# Logic.net
KiCad netlist of a schematic drawn in Altium Designer
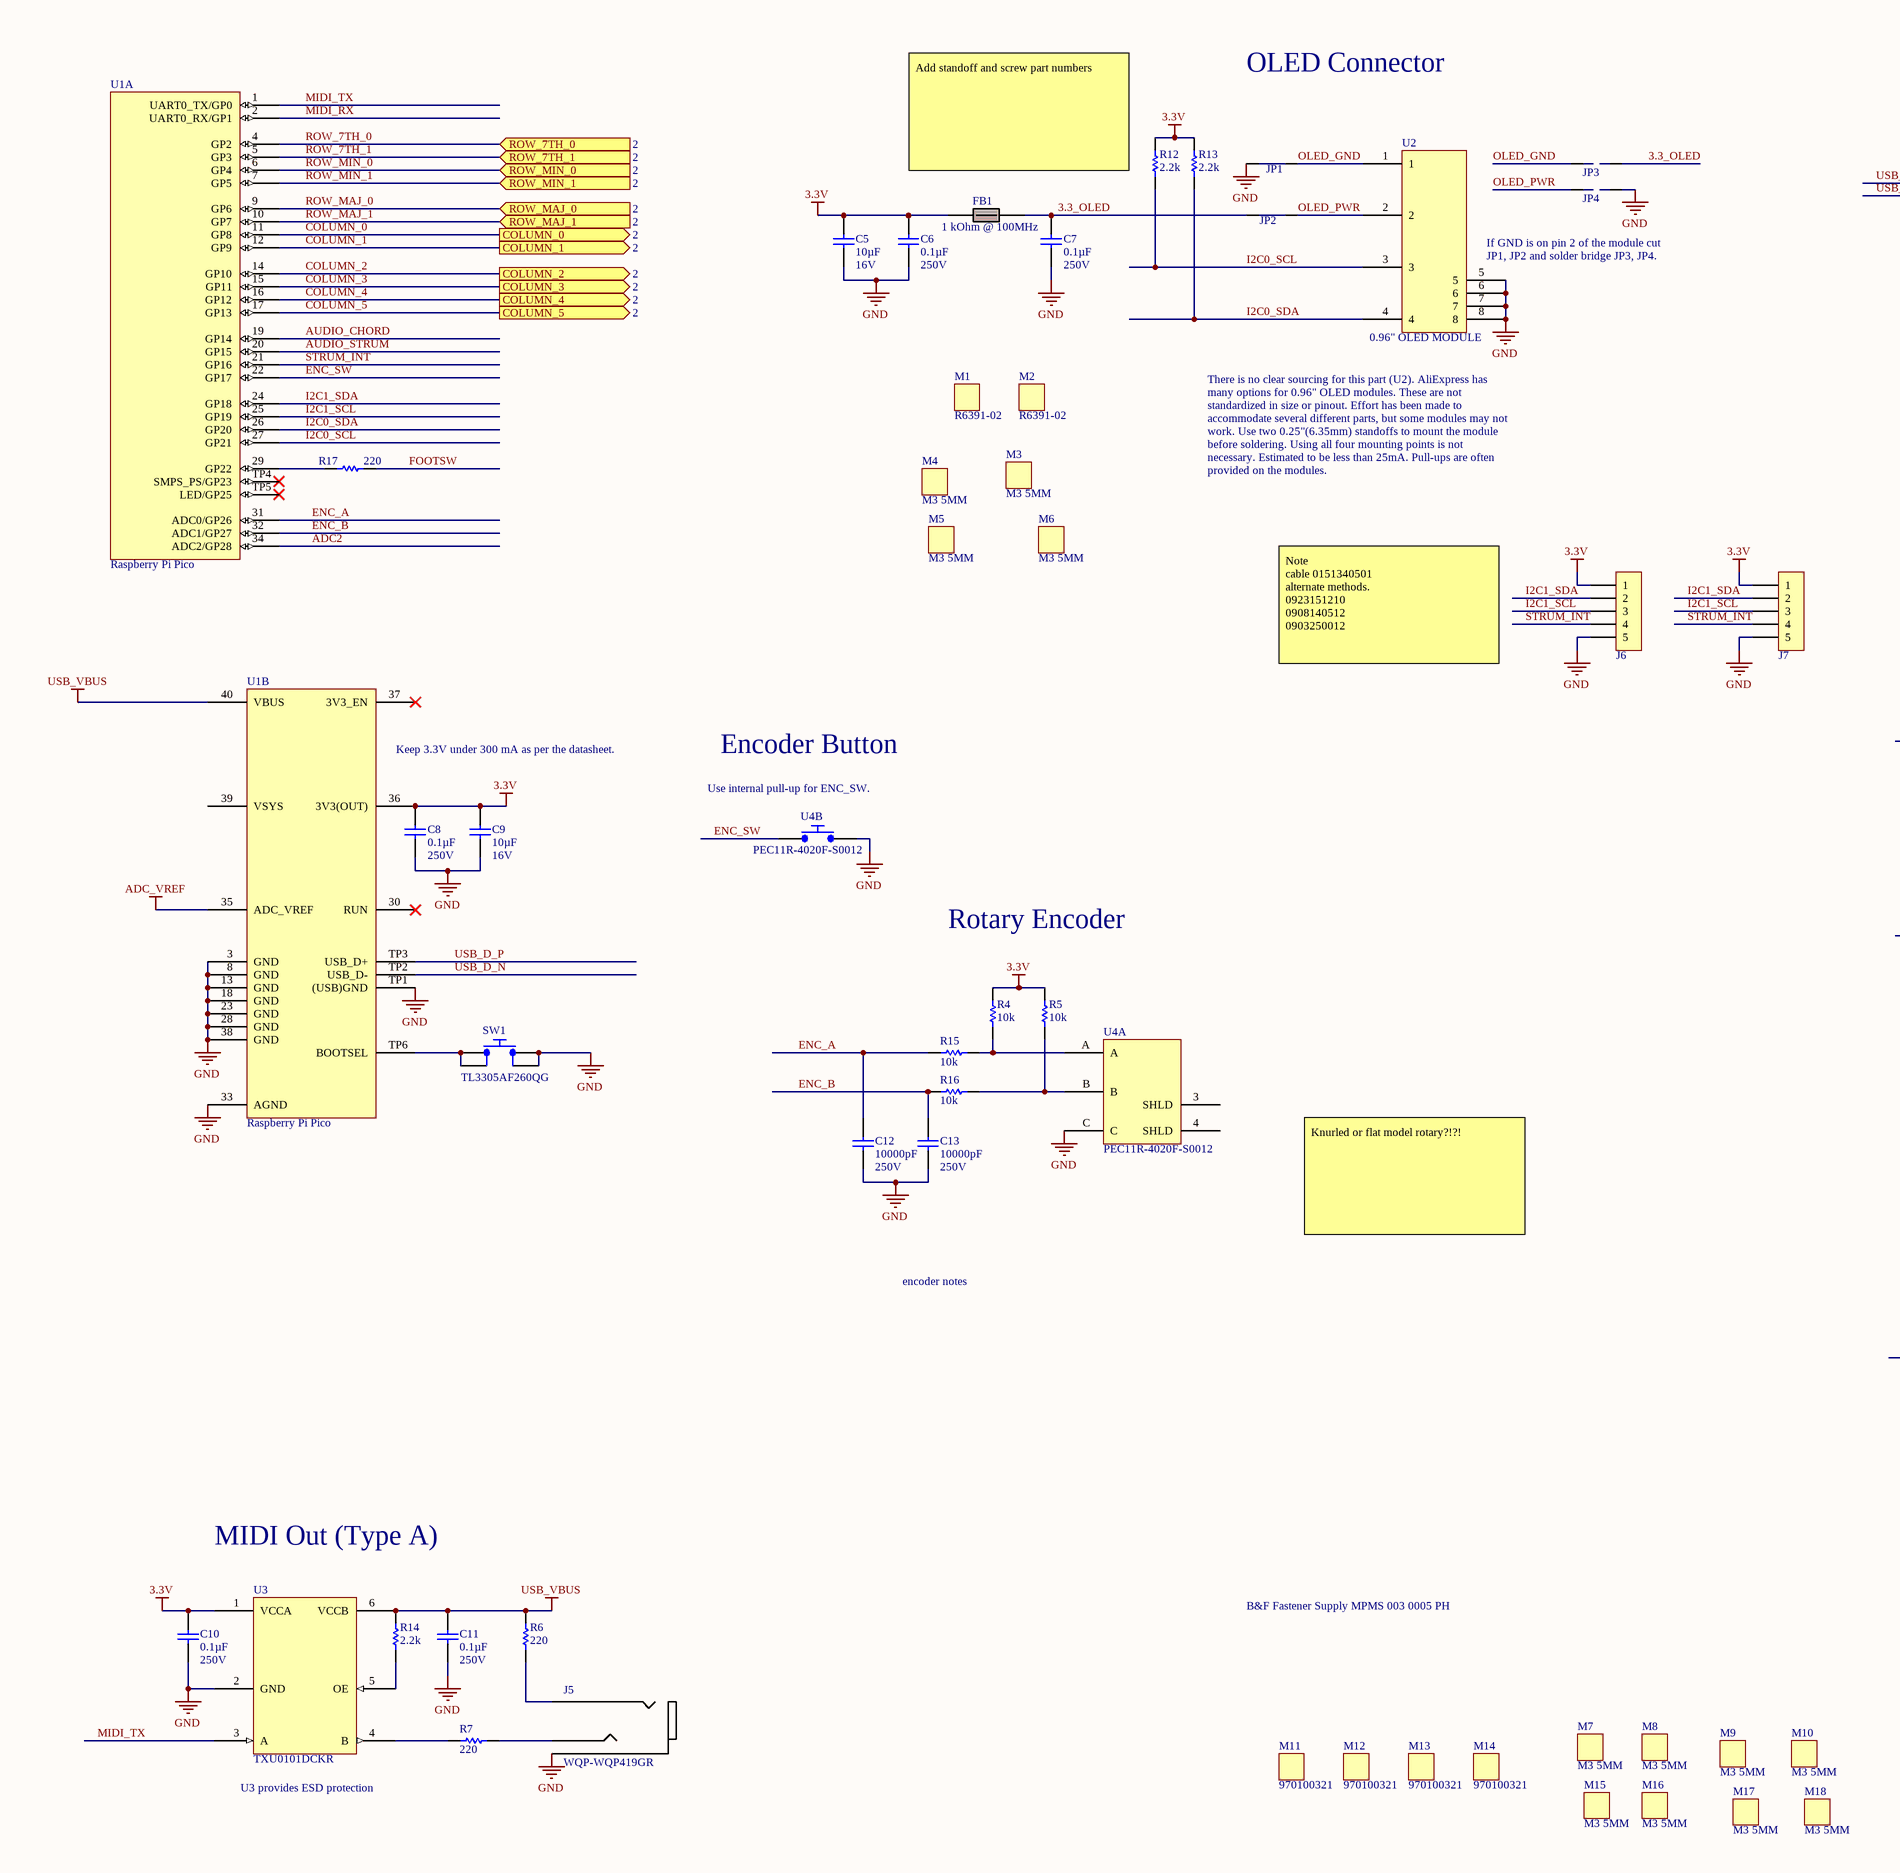
[diagram p0: Logic.SchDoc, left]
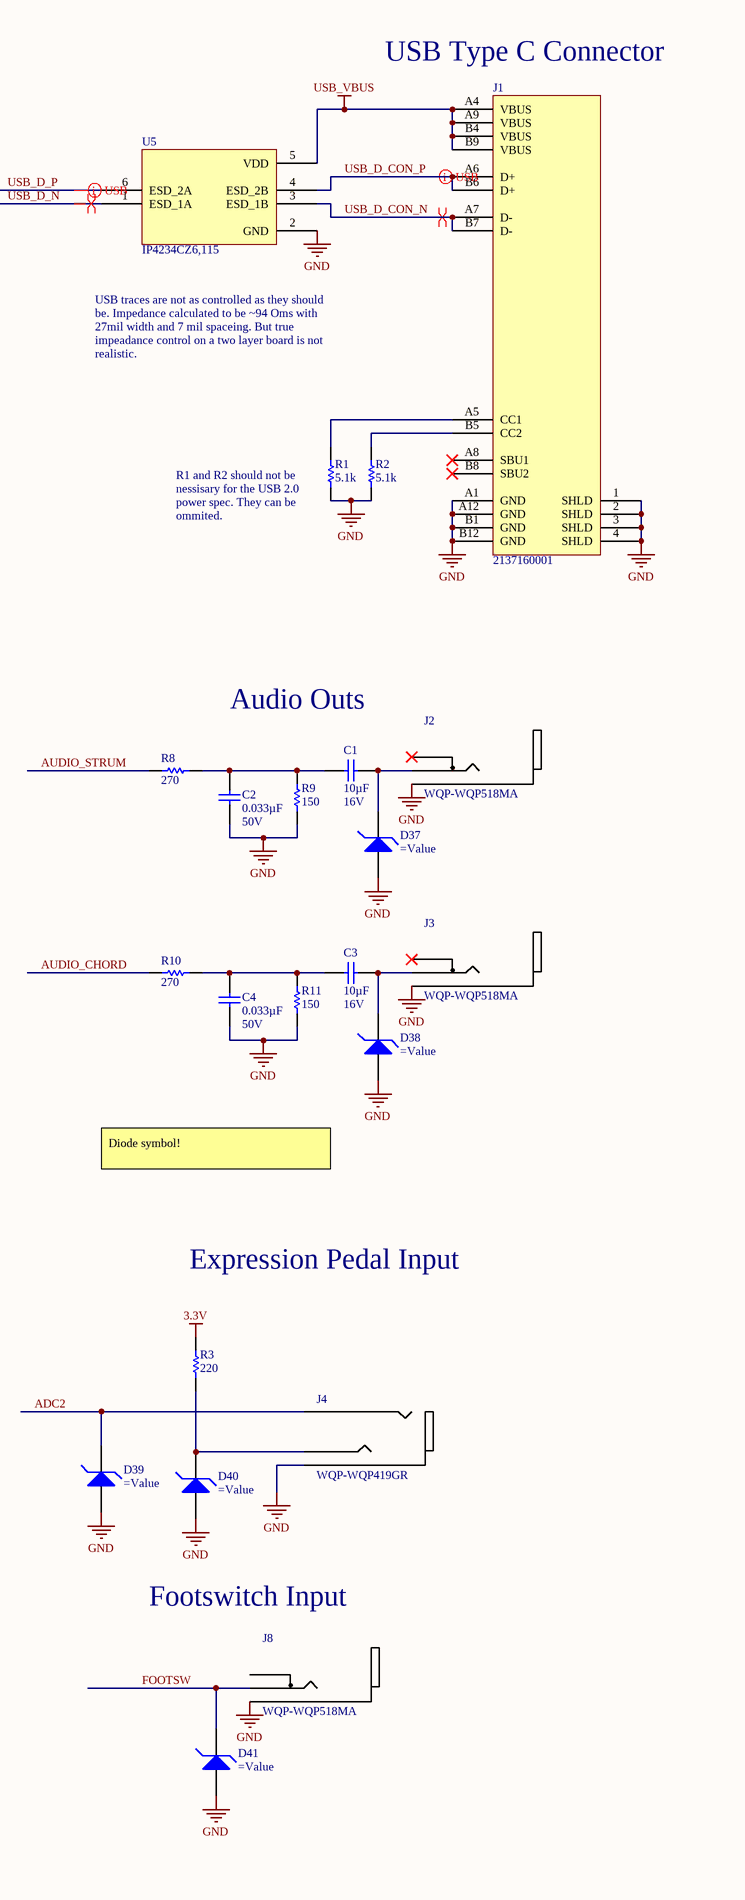
[diagram p1: Logic.SchDoc, right]

(export (version "E")
  (design (tool "Eeschema 10.0.6"))
  (components
    (comp (ref "C1")
      (value "10µF")
      (footprint "Chip0805")
      (description "CAP CER 10UF 16V 10% X5R 0805")
      (fields
        (field (name "VOLTAGE") "16V")
        (field (name "PARTNUMBER") "C2012X5R1C106K125AC")
        (field (name "MANUFACTURER") "TDK Corporation")
      )
      (libsource (lib "Passives") (part "CAP"))
    )
    (comp (ref "C2")
      (value "0.033µF")
      (footprint "Chip0805")
      (description "CAP CER 0.033UF 50V 5% NP0 0805")
      (fields
        (field (name "VOLTAGE") "50V")
        (field (name "PARTNUMBER") "C2012C0G1H333J125AA")
        (field (name "MANUFACTURER") "TDK Corporation")
      )
      (libsource (lib "Passives") (part "CAP"))
    )
    (comp (ref "C3")
      (value "10µF")
      (footprint "Chip0805")
      (description "CAP CER 10UF 16V 10% X5R 0805")
      (fields
        (field (name "VOLTAGE") "16V")
        (field (name "PARTNUMBER") "C2012X5R1C106K125AC")
        (field (name "MANUFACTURER") "TDK Corporation")
      )
      (libsource (lib "Passives") (part "CAP"))
    )
    (comp (ref "C4")
      (value "0.033µF")
      (footprint "Chip0805")
      (description "CAP CER 0.033UF 50V 5% NP0 0805")
      (fields
        (field (name "VOLTAGE") "50V")
        (field (name "PARTNUMBER") "C2012C0G1H333J125AA")
        (field (name "MANUFACTURER") "TDK Corporation")
      )
      (libsource (lib "Passives") (part "CAP"))
    )
    (comp (ref "C5")
      (value "10µF")
      (footprint "Chip0805")
      (description "CAP CER 10UF 16V 10% X5R 0805")
      (fields
        (field (name "VOLTAGE") "16V")
        (field (name "PARTNUMBER") "C2012X5R1C106K125AC")
        (field (name "MANUFACTURER") "TDK Corporation")
      )
      (libsource (lib "Passives") (part "CAP"))
    )
    (comp (ref "C6")
      (value "0.1µF")
      (footprint "Chip0805")
      (description "CAP CER 0.1UF 250V 10% X7T 0805")
      (fields
        (field (name "VOLTAGE") "250V")
        (field (name "PARTNUMBER") "C2012X7T2E104K125AA")
        (field (name "MANUFACTURER") "TDK Corporation")
      )
      (libsource (lib "Passives") (part "CAP"))
    )
    (comp (ref "C7")
      (value "0.1µF")
      (footprint "Chip0805")
      (description "CAP CER 0.1UF 250V 10% X7T 0805")
      (fields
        (field (name "VOLTAGE") "250V")
        (field (name "PARTNUMBER") "C2012X7T2E104K125AA")
        (field (name "MANUFACTURER") "TDK Corporation")
      )
      (libsource (lib "Passives") (part "CAP"))
    )
    (comp (ref "C8")
      (value "0.1µF")
      (footprint "Chip0805")
      (description "CAP CER 0.1UF 250V 10% X7T 0805")
      (fields
        (field (name "VOLTAGE") "250V")
        (field (name "PARTNUMBER") "C2012X7T2E104K125AA")
        (field (name "MANUFACTURER") "TDK Corporation")
      )
      (libsource (lib "Passives") (part "CAP"))
    )
    (comp (ref "C9")
      (value "10µF")
      (footprint "Chip0805")
      (description "CAP CER 10UF 16V 10% X5R 0805")
      (fields
        (field (name "VOLTAGE") "16V")
        (field (name "PARTNUMBER") "C2012X5R1C106K125AC")
        (field (name "MANUFACTURER") "TDK Corporation")
      )
      (libsource (lib "Passives") (part "CAP"))
    )
    (comp (ref "C10")
      (value "0.1µF")
      (footprint "Chip0805")
      (description "CAP CER 0.1UF 250V 10% X7T 0805")
      (fields
        (field (name "VOLTAGE") "250V")
        (field (name "PARTNUMBER") "C2012X7T2E104K125AA")
        (field (name "MANUFACTURER") "TDK Corporation")
      )
      (libsource (lib "Passives") (part "CAP"))
    )
    (comp (ref "C11")
      (value "0.1µF")
      (footprint "Chip0805")
      (description "CAP CER 0.1UF 250V 10% X7T 0805")
      (fields
        (field (name "VOLTAGE") "250V")
        (field (name "PARTNUMBER") "C2012X7T2E104K125AA")
        (field (name "MANUFACTURER") "TDK Corporation")
      )
      (libsource (lib "Passives") (part "CAP"))
    )
    (comp (ref "C12")
      (value "10000pF")
      (footprint "Chip0805")
      (description "CAP CER 10000PF 250V X7R 0805")
      (fields
        (field (name "VOLTAGE") "250V")
        (field (name "PARTNUMBER") "C2012X7R2E103M125AE")
        (field (name "MANUFACTURER") "TDK Corporation")
      )
      (libsource (lib "Passives") (part "CAP"))
    )
    (comp (ref "C13")
      (value "10000pF")
      (footprint "Chip0805")
      (description "CAP CER 10000PF 250V X7R 0805")
      (fields
        (field (name "VOLTAGE") "250V")
        (field (name "PARTNUMBER") "C2012X7R2E103M125AE")
        (field (name "MANUFACTURER") "TDK Corporation")
      )
      (libsource (lib "Passives") (part "CAP"))
    )
    (comp (ref "D37")
      (value "~")
      (footprint "SOD-923")
      (description "TVS DIODE 3.3VWM 10.4VC SOD923")
      (fields (field (name "PARTNUMBER") "SZESD9X3.3ST5G") (field (name "MANUFACTURER") "onsemi"))
      (libsource (lib "Semiconductor") (part "DIODE_ZENER"))
    )
    (comp (ref "D38")
      (value "~")
      (footprint "SOD-923")
      (description "TVS DIODE 3.3VWM 10.4VC SOD923")
      (fields (field (name "PARTNUMBER") "SZESD9X3.3ST5G") (field (name "MANUFACTURER") "onsemi"))
      (libsource (lib "Semiconductor") (part "DIODE_ZENER"))
    )
    (comp (ref "D39")
      (value "~")
      (footprint "SOD-923")
      (description "TVS DIODE 3.3VWM 10.4VC SOD923")
      (fields (field (name "PARTNUMBER") "SZESD9X3.3ST5G") (field (name "MANUFACTURER") "onsemi"))
      (libsource (lib "Semiconductor") (part "DIODE_ZENER"))
    )
    (comp (ref "D40")
      (value "~")
      (footprint "SOD-923")
      (description "TVS DIODE 3.3VWM 10.4VC SOD923")
      (fields (field (name "PARTNUMBER") "SZESD9X3.3ST5G") (field (name "MANUFACTURER") "onsemi"))
      (libsource (lib "Semiconductor") (part "DIODE_ZENER"))
    )
    (comp (ref "D41")
      (value "~")
      (footprint "SOD-923")
      (description "TVS DIODE 3.3VWM 10.4VC SOD923")
      (fields (field (name "PARTNUMBER") "SZESD9X3.3ST5G") (field (name "MANUFACTURER") "onsemi"))
      (libsource (lib "Semiconductor") (part "DIODE_ZENER"))
    )
    (comp (ref "FB1")
      (value "FERRITE")
      (footprint "Chip0805")
      (description "FERRITE BEAD 1000 OHM .20A 0805")
      (fields
        (field (name "IMPEDANCE @ FREQUENCY") "1 kOhm @ 100MHz")
        (field (name "PARTNUMBER") "74279205")
        (field (name "MANUFACTURER") "Wurth Electronics Inc")
      )
      (libsource (lib "Passives") (part "FERRITE"))
    )
    (comp (ref "J1")
      (value "2137160001")
      (footprint "MOLEX_2137160001")
      (description "CONN RCPT USB2.0 TYPE C 24POS RA")
      (fields (field (name "MANUFACTURER") "Molex, LLC"))
      (libsource (lib "Connectors") (part "MOLEX_2137160001"))
    )
    (comp (ref "J2")
      (value "WQP-WQP518MA")
      (footprint "PJ301M-12")
      (description "CONN 3.5mm VIRTICAL MONO w/ NORMAL")
      (fields (field (name "MANUFACTURER") "QingPu"))
      (libsource (lib "Connectors") (part "PJ301M-12"))
    )
    (comp (ref "J3")
      (value "WQP-WQP518MA")
      (footprint "PJ301M-12")
      (description "CONN 3.5mm VIRTICAL MONO w/ NORMAL")
      (fields (field (name "MANUFACTURER") "QingPu"))
      (libsource (lib "Connectors") (part "PJ301M-12"))
    )
    (comp (ref "J4")
      (value "WQP-WQP419GR")
      (footprint "PJ366ST")
      (description "CONN 3.5mm VIRTICAL STEREO")
      (fields (field (name "MANUFACTURER") "QingPu"))
      (libsource (lib "Connectors") (part "PJ366ST"))
    )
    (comp (ref "J5")
      (value "WQP-WQP419GR")
      (footprint "PJ366ST")
      (description "CONN 3.5mm VIRTICAL STEREO")
      (fields (field (name "MANUFACTURER") "QingPu"))
      (libsource (lib "Connectors") (part "PJ366ST"))
    )
    (comp (ref "J6")
      (value "0532610571")
      (footprint "MOLEX_0532610571")
      (description "CONN HEADER SMD R/A 5POS 1.25MM")
      (fields (field (name "MANUFACTURER PART NUMBER") "WM7623CT-ND") (field (name "MANUFACTURER") "Molex"))
      (libsource (lib "Connectors") (part "HEADER_1x5"))
    )
    (comp (ref "J7")
      (value "250010502")
      (footprint "HEADER_1x5_100mil_NP")
      (description "CABLE 5POS .100 JUMPER 2 INCHES")
      (fields (field (name "MANUFACTURER") "Molex Inc"))
      (libsource (lib "Cable_Assemblies") (part "HEADER_1x5"))
    )
    (comp (ref "J8")
      (value "WQP-WQP518MA")
      (footprint "PJ301M-12")
      (description "CONN 3.5mm VIRTICAL MONO w/ NORMAL")
      (fields (field (name "MANUFACTURER") "QingPu"))
      (libsource (lib "Connectors") (part "PJ301M-12"))
    )
    (comp (ref "JP1")
      (value "JUMMPER_NC_0805")
      (footprint "JUMMPER_NC_0805")
      (libsource (lib "Mechanical") (part "JUMPER_NC"))
    )
    (comp (ref "JP2")
      (value "JUMMPER_NC_0805")
      (footprint "JUMMPER_NC_0805")
      (libsource (lib "Mechanical") (part "JUMPER_NC"))
    )
    (comp (ref "JP3")
      (value "JUMMPER_NO_0805")
      (footprint "JUMMPER_NO_0805")
      (libsource (lib "Mechanical") (part "JUMPER_NO"))
    )
    (comp (ref "JP4")
      (value "JUMMPER_NO_0805")
      (footprint "JUMMPER_NO_0805")
      (libsource (lib "Mechanical") (part "JUMPER_NO"))
    )
    (comp (ref "M1")
      (value "R6391-02")
      (description "HEX STANDOFF M3X0.5 BRASS 1/4\"")
      (fields (field (name "MANUFACTURER") "Harwin Inc."))
      (libsource (lib "Mechanical") (part "MECH_NO_FP"))
    )
    (comp (ref "M2")
      (value "R6391-02")
      (description "HEX STANDOFF M3X0.5 BRASS 1/4\"")
      (fields (field (name "MANUFACTURER") "Harwin Inc."))
      (libsource (lib "Mechanical") (part "MECH_NO_FP"))
    )
    (comp (ref "M3")
      (value "M3 5MM")
      (description "MACH SCREW PAN HEAD PHILLIPS M3 5MM")
      (libsource (lib "Mechanical") (part "MECH_NO_FP"))
    )
    (comp (ref "M4")
      (value "M3 5MM")
      (description "MACH SCREW PAN HEAD PHILLIPS M3 5MM")
      (libsource (lib "Mechanical") (part "MECH_NO_FP"))
    )
    (comp (ref "M5")
      (value "M3 5MM")
      (description "MACH SCREW PAN HEAD PHILLIPS M3 5MM")
      (libsource (lib "Mechanical") (part "MECH_NO_FP"))
    )
    (comp (ref "M6")
      (value "M3 5MM")
      (description "MACH SCREW PAN HEAD PHILLIPS M3 5MM")
      (libsource (lib "Mechanical") (part "MECH_NO_FP"))
    )
    (comp (ref "M7")
      (value "M3 5MM")
      (description "MACH SCREW PAN HEAD PHILLIPS M3 5MM")
      (libsource (lib "Mechanical") (part "MECH_NO_FP"))
    )
    (comp (ref "M8")
      (value "M3 5MM")
      (description "MACH SCREW PAN HEAD PHILLIPS M3 5MM")
      (libsource (lib "Mechanical") (part "MECH_NO_FP"))
    )
    (comp (ref "M9")
      (value "M3 5MM")
      (description "MACH SCREW PAN HEAD PHILLIPS M3 5MM")
      (libsource (lib "Mechanical") (part "MECH_NO_FP"))
    )
    (comp (ref "M10")
      (value "M3 5MM")
      (description "MACH SCREW PAN HEAD PHILLIPS M3 5MM")
      (libsource (lib "Mechanical") (part "MECH_NO_FP"))
    )
    (comp (ref "M11")
      (value "970100321")
      (description "HEX STANDOFF M3X0.5 STEEL 10MM")
      (fields (field (name "MANUFACTURER") "Würth Elektronik"))
      (libsource (lib "Mechanical") (part "MECH_NO_FP"))
    )
    (comp (ref "M12")
      (value "970100321")
      (description "HEX STANDOFF M3X0.5 STEEL 10MM")
      (fields (field (name "MANUFACTURER") "Würth Elektronik"))
      (libsource (lib "Mechanical") (part "MECH_NO_FP"))
    )
    (comp (ref "M13")
      (value "970100321")
      (description "HEX STANDOFF M3X0.5 STEEL 10MM")
      (fields (field (name "MANUFACTURER") "Würth Elektronik"))
      (libsource (lib "Mechanical") (part "MECH_NO_FP"))
    )
    (comp (ref "M14")
      (value "970100321")
      (description "HEX STANDOFF M3X0.5 STEEL 10MM")
      (fields (field (name "MANUFACTURER") "Würth Elektronik"))
      (libsource (lib "Mechanical") (part "MECH_NO_FP"))
    )
    (comp (ref "M15")
      (value "M3 5MM")
      (description "MACH SCREW PAN HEAD PHILLIPS M3 5MM")
      (libsource (lib "Mechanical") (part "MECH_NO_FP"))
    )
    (comp (ref "M16")
      (value "M3 5MM")
      (description "MACH SCREW PAN HEAD PHILLIPS M3 5MM")
      (libsource (lib "Mechanical") (part "MECH_NO_FP"))
    )
    (comp (ref "M17")
      (value "M3 5MM")
      (description "MACH SCREW PAN HEAD PHILLIPS M3 5MM")
      (libsource (lib "Mechanical") (part "MECH_NO_FP"))
    )
    (comp (ref "M18")
      (value "M3 5MM")
      (description "MACH SCREW PAN HEAD PHILLIPS M3 5MM")
      (libsource (lib "Mechanical") (part "MECH_NO_FP"))
    )
    (comp (ref "R1")
      (value "5.1k")
      (footprint "Chip0603")
      (description "RES 5.10K OHM 1/10W 1% 0603 SMD")
      (fields (field (name "PARTNUMBER") "CRCW06035K10FKEA") (field (name "MANUFACTURER") "Vishay Dale"))
      (libsource (lib "Passives") (part "RES"))
    )
    (comp (ref "R2")
      (value "5.1k")
      (footprint "Chip0603")
      (description "RES 5.10K OHM 1/10W 1% 0603 SMD")
      (fields (field (name "PARTNUMBER") "CRCW06035K10FKEA") (field (name "MANUFACTURER") "Vishay Dale"))
      (libsource (lib "Passives") (part "RES"))
    )
    (comp (ref "R3")
      (value "220")
      (footprint "Chip0805")
      (description "RES 220 OHM 1/8W 1% 0805 SMD")
      (fields (field (name "PARTNUMBER") "CRCW0805220RFKEA") (field (name "MANUFACTURER") "Vishay Dale"))
      (libsource (lib "Passives") (part "RES"))
    )
    (comp (ref "R4")
      (value "10k")
      (footprint "Chip0805")
      (description "RES 10.0K OHM 1/8W 1% 0805 SMD")
      (fields (field (name "PARTNUMBER") "CRCW080510K0FKEA") (field (name "MANUFACTURER") "Vishay Dale"))
      (libsource (lib "Passives") (part "RES"))
    )
    (comp (ref "R5")
      (value "10k")
      (footprint "Chip0805")
      (description "RES 10.0K OHM 1/8W 1% 0805 SMD")
      (fields (field (name "PARTNUMBER") "CRCW080510K0FKEA") (field (name "MANUFACTURER") "Vishay Dale"))
      (libsource (lib "Passives") (part "RES"))
    )
    (comp (ref "R6")
      (value "220")
      (footprint "Chip0805")
      (description "RES 220 OHM 1/8W 1% 0805 SMD")
      (fields (field (name "PARTNUMBER") "CRCW0805220RFKEA") (field (name "MANUFACTURER") "Vishay Dale"))
      (libsource (lib "Passives") (part "RES"))
    )
    (comp (ref "R7")
      (value "220")
      (footprint "Chip0805")
      (description "RES 220 OHM 1/8W 1% 0805 SMD")
      (fields (field (name "PARTNUMBER") "CRCW0805220RFKEA") (field (name "MANUFACTURER") "Vishay Dale"))
      (libsource (lib "Passives") (part "RES"))
    )
    (comp (ref "R8")
      (value "270")
      (footprint "Chip0805")
      (description "RES 270 OHM 1/8W 1% 0805 SMD")
      (fields (field (name "PARTNUMBER") "CRCW0805270RFKEA") (field (name "MANUFACTURER") "Vishay Dale"))
      (libsource (lib "Passives") (part "RES"))
    )
    (comp (ref "R9")
      (value "150")
      (footprint "Chip0805")
      (description "RES 150 OHM 1/8W 1% 0805 SMD")
      (fields (field (name "PARTNUMBER") "CRCW0805150RFKEA") (field (name "MANUFACTURER") "Vishay Dale"))
      (libsource (lib "Passives") (part "RES"))
    )
    (comp (ref "R10")
      (value "270")
      (footprint "Chip0805")
      (description "RES 270 OHM 1/8W 1% 0805 SMD")
      (fields (field (name "PARTNUMBER") "CRCW0805270RFKEA") (field (name "MANUFACTURER") "Vishay Dale"))
      (libsource (lib "Passives") (part "RES"))
    )
    (comp (ref "R11")
      (value "150")
      (footprint "Chip0805")
      (description "RES 150 OHM 1/8W 1% 0805 SMD")
      (fields (field (name "PARTNUMBER") "CRCW0805150RFKEA") (field (name "MANUFACTURER") "Vishay Dale"))
      (libsource (lib "Passives") (part "RES"))
    )
    (comp (ref "R12")
      (value "2.2k")
      (footprint "Chip0805")
      (description "RES 2.20K OHM 1/8W 1% 0805 SMD")
      (fields (field (name "PARTNUMBER") "CRCW08052K20FKEA") (field (name "MANUFACTURER") "Vishay Dale"))
      (libsource (lib "Passives") (part "RES"))
    )
    (comp (ref "R13")
      (value "2.2k")
      (footprint "Chip0805")
      (description "RES 2.20K OHM 1/8W 1% 0805 SMD")
      (fields (field (name "PARTNUMBER") "CRCW08052K20FKEA") (field (name "MANUFACTURER") "Vishay Dale"))
      (libsource (lib "Passives") (part "RES"))
    )
    (comp (ref "R14")
      (value "2.2k")
      (footprint "Chip0805")
      (description "RES 2.20K OHM 1/8W 1% 0805 SMD")
      (fields (field (name "PARTNUMBER") "CRCW08052K20FKEA") (field (name "MANUFACTURER") "Vishay Dale"))
      (libsource (lib "Passives") (part "RES"))
    )
    (comp (ref "R15")
      (value "10k")
      (footprint "Chip0805")
      (description "RES 10.0K OHM 1/8W 1% 0805 SMD")
      (fields (field (name "PARTNUMBER") "CRCW080510K0FKEA") (field (name "MANUFACTURER") "Vishay Dale"))
      (libsource (lib "Passives") (part "RES"))
    )
    (comp (ref "R16")
      (value "10k")
      (footprint "Chip0805")
      (description "RES 10.0K OHM 1/8W 1% 0805 SMD")
      (fields (field (name "PARTNUMBER") "CRCW080510K0FKEA") (field (name "MANUFACTURER") "Vishay Dale"))
      (libsource (lib "Passives") (part "RES"))
    )
    (comp (ref "R17")
      (value "220")
      (footprint "Chip0805")
      (description "RES 220 OHM 1/8W 1% 0805 SMD")
      (fields (field (name "PARTNUMBER") "CRCW0805220RFKEA") (field (name "MANUFACTURER") "Vishay Dale"))
      (libsource (lib "Passives") (part "RES"))
    )
    (comp (ref "SW1")
      (value "TL3305AF260QG")
      (footprint "E_SWITCH_TL3305")
      (description "SWITCH TACTILE SPST-NO 50MA 12V")
      (fields (field (name "MANUFACTURER") "E-Switch"))
      (libsource (lib "Switches") (part "SWITCH_SPST_PUSH_NO_4"))
    )
    (comp (ref "U1")
      (value "Raspberry Pi Pico")
      (footprint "RASPBERRY_PI_PICO")
      (description "RASPBERRY PI PICO RP2040 BOARD")
      (fields (field (name "MANUFACTURER PART NUMBER") "SC0915") (field (name "MANUFACTURER") "Raspberry Pi"))
      (libsource (lib "ICs") (part "PI_PICO_SC0915"))
    )
    (comp (ref "U2")
      (value "0.96\" OLED MODULE")
      (footprint "OLEDp96MOD_BOARD_MOUNT")
      (description "0.96\" I2C OLED MODULE")
      (libsource (lib "ICs") (part "OLEDp96MOD_BOARD_MOUNT"))
    )
    (comp (ref "U3")
      (value "TXU0101DCKR")
      (footprint "6-TSSOP")
      (description "SINGLE CHANNEL FIXED-DIRECTION L")
      (fields (field (name "MANUFACTURER") "Texas Instruments"))
      (libsource (lib "ICs") (part "TI_TXU0101"))
    )
    (comp (ref "U4")
      (value "PEC11R-4020F-S0012")
      (footprint "BOURNS_PEC11R-4020F-S")
      (description "ROTARY ENCODER MECHANICAL 12PPR")
      (fields (field (name "MANUFACTURER") "Bourns Inc."))
      (libsource (lib "Miscellaneous") (part "ROTARY_ENCODER_SWITCH"))
    )
    (comp (ref "U5")
      (value "IP4234CZ6,115")
      (footprint "6-TSOP")
      (description "TVS DIODE 5.5VWM 6TSOP")
      (fields (field (name "MANUFACTURER") "Nexperia USA Inc."))
      (libsource (lib "Semiconductor") (part "NEXPERIA_IP4234CZ6"))
    )
  )
  (nets
    (net (code "1") (name "/3.3_OLED") (class "Default")
      (node (ref "C7") (pin "2") (pinfunction "2_2") (pintype "passive"))
      (node (ref "FB1") (pin "2") (pinfunction "2_2") (pintype "passive"))
      (node (ref "JP2") (pin "1") (pinfunction "1_1") (pintype "passive"))
      (node (ref "JP3") (pin "1") (pinfunction "1_1") (pintype "passive"))
    )
    (net (code "2") (name "/ADC2") (class "Default")
      (node (ref "D39") (pin "1") (pinfunction "K_1") (pintype "passive"))
      (node (ref "J4") (pin "3") (pinfunction "3_3") (pintype "passive"))
      (node (ref "U1") (pin "34") (pinfunction "ADC2/GP28_34") (pintype "bidirectional"))
    )
    (net (code "3") (name "/AUDIO_CHORD") (class "Default")
      (node (ref "R10") (pin "1") (pinfunction "1_1") (pintype "passive"))
      (node (ref "U1") (pin "19") (pinfunction "GP14_19") (pintype "bidirectional"))
    )
    (net (code "4") (name "/AUDIO_STRUM") (class "Default")
      (node (ref "R8") (pin "1") (pinfunction "1_1") (pintype "passive"))
      (node (ref "U1") (pin "20") (pinfunction "GP15_20") (pintype "bidirectional"))
    )
    (net (code "5") (name "/COLUMN_0") (class "Default")
      (node (ref "U1") (pin "11") (pinfunction "GP8_11") (pintype "bidirectional"))
    )
    (net (code "6") (name "/COLUMN_1") (class "Default")
      (node (ref "U1") (pin "12") (pinfunction "GP9_12") (pintype "bidirectional"))
    )
    (net (code "7") (name "/COLUMN_2") (class "Default")
      (node (ref "U1") (pin "14") (pinfunction "GP10_14") (pintype "bidirectional"))
    )
    (net (code "8") (name "/COLUMN_3") (class "Default")
      (node (ref "U1") (pin "15") (pinfunction "GP11_15") (pintype "bidirectional"))
    )
    (net (code "9") (name "/COLUMN_4") (class "Default")
      (node (ref "U1") (pin "16") (pinfunction "GP12_16") (pintype "bidirectional"))
    )
    (net (code "10") (name "/COLUMN_5") (class "Default")
      (node (ref "U1") (pin "17") (pinfunction "GP13_17") (pintype "bidirectional"))
    )
    (net (code "11") (name "/ENC_A") (class "Default")
      (node (ref "C12") (pin "2") (pinfunction "2_2") (pintype "passive"))
      (node (ref "R15") (pin "2") (pinfunction "2_2") (pintype "passive"))
      (node (ref "U1") (pin "31") (pinfunction "ADC0/GP26_31") (pintype "bidirectional"))
    )
    (net (code "12") (name "/ENC_B") (class "Default")
      (node (ref "C13") (pin "2") (pinfunction "2_2") (pintype "passive"))
      (node (ref "R16") (pin "2") (pinfunction "2_2") (pintype "passive"))
      (node (ref "U1") (pin "32") (pinfunction "ADC1/GP27_32") (pintype "bidirectional"))
    )
    (net (code "13") (name "/ENC_SW") (class "Default")
      (node (ref "U1") (pin "22") (pinfunction "GP17_22") (pintype "bidirectional"))
      (node (ref "U4") (pin "2") (pinfunction "2_2") (pintype "passive"))
    )
    (net (code "14") (name "/FOOTSW") (class "Default")
      (node (ref "D41") (pin "1") (pinfunction "K_1") (pintype "passive"))
      (node (ref "J8") (pin "2") (pinfunction "2_2") (pintype "passive"))
      (node (ref "R17") (pin "1") (pinfunction "1_1") (pintype "passive"))
    )
    (net (code "15") (name "/I2C0_SCL") (class "Default")
      (node (ref "R12") (pin "1") (pinfunction "1_1") (pintype "passive"))
      (node (ref "U1") (pin "27") (pinfunction "GP21_27") (pintype "bidirectional"))
      (node (ref "U2") (pin "3") (pinfunction "3_3") (pintype "passive"))
    )
    (net (code "16") (name "/I2C0_SDA") (class "Default")
      (node (ref "R13") (pin "1") (pinfunction "1_1") (pintype "passive"))
      (node (ref "U1") (pin "26") (pinfunction "GP20_26") (pintype "bidirectional"))
      (node (ref "U2") (pin "4") (pinfunction "4_4") (pintype "passive"))
    )
    (net (code "17") (name "/I2C1_SCL") (class "Default")
      (node (ref "J6") (pin "3") (pinfunction "3_3") (pintype "passive"))
      (node (ref "J7") (pin "3") (pinfunction "3_3") (pintype "passive"))
      (node (ref "U1") (pin "25") (pinfunction "GP19_25") (pintype "bidirectional"))
    )
    (net (code "18") (name "/I2C1_SDA") (class "Default")
      (node (ref "J6") (pin "2") (pinfunction "2_2") (pintype "passive"))
      (node (ref "J7") (pin "2") (pinfunction "2_2") (pintype "passive"))
      (node (ref "U1") (pin "24") (pinfunction "GP18_24") (pintype "bidirectional"))
    )
    (net (code "19") (name "/MIDI_RX") (class "Default")
      (node (ref "U1") (pin "2") (pinfunction "UART0_RX/GP1_2") (pintype "bidirectional"))
    )
    (net (code "20") (name "/MIDI_TX") (class "Default")
      (node (ref "U1") (pin "1") (pinfunction "UART0_TX/GP0_1") (pintype "bidirectional"))
      (node (ref "U3") (pin "3") (pinfunction "A_3") (pintype "input"))
    )
    (net (code "21") (name "/OLED_GND") (class "Default")
      (node (ref "JP1") (pin "2") (pinfunction "2_2") (pintype "passive"))
      (node (ref "JP3") (pin "2") (pinfunction "2_2") (pintype "passive"))
      (node (ref "U2") (pin "1") (pinfunction "1_1") (pintype "passive"))
    )
    (net (code "22") (name "/OLED_PWR") (class "Default")
      (node (ref "JP2") (pin "2") (pinfunction "2_2") (pintype "passive"))
      (node (ref "JP4") (pin "2") (pinfunction "2_2") (pintype "passive"))
      (node (ref "U2") (pin "2") (pinfunction "2_2") (pintype "passive"))
    )
    (net (code "23") (name "/ROW_7TH_0") (class "Default")
      (node (ref "U1") (pin "4") (pinfunction "GP2_4") (pintype "bidirectional"))
    )
    (net (code "24") (name "/ROW_7TH_1") (class "Default")
      (node (ref "U1") (pin "5") (pinfunction "GP3_5") (pintype "bidirectional"))
    )
    (net (code "25") (name "/ROW_MAJ_0") (class "Default")
      (node (ref "U1") (pin "9") (pinfunction "GP6_9") (pintype "bidirectional"))
    )
    (net (code "26") (name "/ROW_MAJ_1") (class "Default")
      (node (ref "U1") (pin "10") (pinfunction "GP7_10") (pintype "bidirectional"))
    )
    (net (code "27") (name "/ROW_MIN_0") (class "Default")
      (node (ref "U1") (pin "6") (pinfunction "GP4_6") (pintype "bidirectional"))
    )
    (net (code "28") (name "/ROW_MIN_1") (class "Default")
      (node (ref "U1") (pin "7") (pinfunction "GP5_7") (pintype "bidirectional"))
    )
    (net (code "29") (name "/STRUM_INT") (class "Default")
      (node (ref "J6") (pin "4") (pinfunction "4_4") (pintype "passive"))
      (node (ref "J7") (pin "4") (pinfunction "4_4") (pintype "passive"))
      (node (ref "U1") (pin "21") (pinfunction "GP16_21") (pintype "bidirectional"))
    )
    (net (code "30") (name "/USB_D_CON_N") (class "Default")
      (node (ref "J1") (pin "A7") (pinfunction "D-_A7") (pintype "passive"))
      (node (ref "J1") (pin "B7") (pinfunction "D-_B7") (pintype "passive"))
      (node (ref "U5") (pin "3") (pinfunction "ESD_1B_3") (pintype "passive"))
    )
    (net (code "31") (name "/USB_D_CON_P") (class "Default")
      (node (ref "J1") (pin "A6") (pinfunction "D+_A6") (pintype "passive"))
      (node (ref "J1") (pin "B6") (pinfunction "D+_B6") (pintype "passive"))
      (node (ref "U5") (pin "4") (pinfunction "ESD_2B_4") (pintype "passive"))
    )
    (net (code "32") (name "/USB_D_N") (class "Default")
      (node (ref "U1") (pin "TP2") (pinfunction "USB_D-_TP2") (pintype "passive"))
      (node (ref "U5") (pin "1") (pinfunction "ESD_1A_1") (pintype "passive"))
    )
    (net (code "33") (name "/USB_D_P") (class "Default")
      (node (ref "U1") (pin "TP3") (pinfunction "USB_D+_TP3") (pintype "passive"))
      (node (ref "U5") (pin "6") (pinfunction "ESD_2A_6") (pintype "passive"))
    )
    (net (code "34") (name "3.3V") (class "Default")
      (node (ref "C10") (pin "2") (pinfunction "2_2") (pintype "passive"))
      (node (ref "C5") (pin "2") (pinfunction "2_2") (pintype "passive"))
      (node (ref "C6") (pin "2") (pinfunction "2_2") (pintype "passive"))
      (node (ref "C8") (pin "2") (pinfunction "2_2") (pintype "passive"))
      (node (ref "C9") (pin "2") (pinfunction "2_2") (pintype "passive"))
      (node (ref "FB1") (pin "1") (pinfunction "1_1") (pintype "passive"))
      (node (ref "J6") (pin "1") (pinfunction "1_1") (pintype "passive"))
      (node (ref "J7") (pin "1") (pinfunction "1_1") (pintype "passive"))
      (node (ref "R12") (pin "2") (pinfunction "2_2") (pintype "passive"))
      (node (ref "R13") (pin "2") (pinfunction "2_2") (pintype "passive"))
      (node (ref "R3") (pin "2") (pinfunction "2_2") (pintype "passive"))
      (node (ref "R4") (pin "2") (pinfunction "2_2") (pintype "passive"))
      (node (ref "R5") (pin "2") (pinfunction "2_2") (pintype "passive"))
      (node (ref "U1") (pin "36") (pinfunction "3V3(OUT)_36") (pintype "passive"))
      (node (ref "U3") (pin "1") (pinfunction "VCCA_1") (pintype "passive"))
    )
    (net (code "35") (name "ADC_VREF") (class "Default")
      (node (ref "U1") (pin "35") (pinfunction "ADC_VREF_35") (pintype "passive"))
    )
    (net (code "36") (name "GND") (class "Default")
      (node (ref "C10") (pin "1") (pinfunction "1_1") (pintype "passive"))
      (node (ref "C11") (pin "1") (pinfunction "1_1") (pintype "passive"))
      (node (ref "C12") (pin "1") (pinfunction "1_1") (pintype "passive"))
      (node (ref "C13") (pin "1") (pinfunction "1_1") (pintype "passive"))
      (node (ref "C2") (pin "1") (pinfunction "1_1") (pintype "passive"))
      (node (ref "C4") (pin "1") (pinfunction "1_1") (pintype "passive"))
      (node (ref "C5") (pin "1") (pinfunction "1_1") (pintype "passive"))
      (node (ref "C6") (pin "1") (pinfunction "1_1") (pintype "passive"))
      (node (ref "C7") (pin "1") (pinfunction "1_1") (pintype "passive"))
      (node (ref "C8") (pin "1") (pinfunction "1_1") (pintype "passive"))
      (node (ref "C9") (pin "1") (pinfunction "1_1") (pintype "passive"))
      (node (ref "D37") (pin "2") (pinfunction "A_2") (pintype "passive"))
      (node (ref "D38") (pin "2") (pinfunction "A_2") (pintype "passive"))
      (node (ref "D39") (pin "2") (pinfunction "A_2") (pintype "passive"))
      (node (ref "D40") (pin "2") (pinfunction "A_2") (pintype "passive"))
      (node (ref "D41") (pin "2") (pinfunction "A_2") (pintype "passive"))
      (node (ref "J1") (pin "1") (pinfunction "SHLD_1") (pintype "passive"))
      (node (ref "J1") (pin "2") (pinfunction "SHLD_2") (pintype "passive"))
      (node (ref "J1") (pin "3") (pinfunction "SHLD_3") (pintype "passive"))
      (node (ref "J1") (pin "4") (pinfunction "SHLD_4") (pintype "passive"))
      (node (ref "J1") (pin "A1") (pinfunction "GND_A1") (pintype "passive"))
      (node (ref "J1") (pin "A12") (pinfunction "GND_A12") (pintype "passive"))
      (node (ref "J1") (pin "B1") (pinfunction "GND_B1") (pintype "passive"))
      (node (ref "J1") (pin "B12") (pinfunction "GND_B12") (pintype "passive"))
      (node (ref "J2") (pin "1") (pinfunction "1_1") (pintype "passive"))
      (node (ref "J3") (pin "1") (pinfunction "1_1") (pintype "passive"))
      (node (ref "J4") (pin "1") (pinfunction "1_1") (pintype "passive"))
      (node (ref "J5") (pin "1") (pinfunction "1_1") (pintype "passive"))
      (node (ref "J6") (pin "5") (pinfunction "5_5") (pintype "passive"))
      (node (ref "J7") (pin "5") (pinfunction "5_5") (pintype "passive"))
      (node (ref "J8") (pin "1") (pinfunction "1_1") (pintype "passive"))
      (node (ref "JP1") (pin "1") (pinfunction "1_1") (pintype "passive"))
      (node (ref "JP4") (pin "1") (pinfunction "1_1") (pintype "passive"))
      (node (ref "R1") (pin "1") (pinfunction "1_1") (pintype "passive"))
      (node (ref "R11") (pin "1") (pinfunction "1_1") (pintype "passive"))
      (node (ref "R2") (pin "1") (pinfunction "1_1") (pintype "passive"))
      (node (ref "R9") (pin "1") (pinfunction "1_1") (pintype "passive"))
      (node (ref "SW1") (pin "3") (pinfunction "3_3") (pintype "passive"))
      (node (ref "SW1") (pin "4") (pinfunction "4_4") (pintype "passive"))
      (node (ref "U1") (pin "13") (pinfunction "GND_13") (pintype "passive"))
      (node (ref "U1") (pin "18") (pinfunction "GND_18") (pintype "passive"))
      (node (ref "U1") (pin "23") (pinfunction "GND_23") (pintype "passive"))
      (node (ref "U1") (pin "28") (pinfunction "GND_28") (pintype "passive"))
      (node (ref "U1") (pin "3") (pinfunction "GND_3") (pintype "passive"))
      (node (ref "U1") (pin "33") (pinfunction "AGND_33") (pintype "passive"))
      (node (ref "U1") (pin "38") (pinfunction "GND_38") (pintype "passive"))
      (node (ref "U1") (pin "8") (pinfunction "GND_8") (pintype "passive"))
      (node (ref "U1") (pin "TP1") (pinfunction "(USB)GND_TP1") (pintype "passive"))
      (node (ref "U2") (pin "5") (pinfunction "5_5") (pintype "passive"))
      (node (ref "U2") (pin "6") (pinfunction "6_6") (pintype "passive"))
      (node (ref "U2") (pin "7") (pinfunction "7_7") (pintype "passive"))
      (node (ref "U2") (pin "8") (pinfunction "8_8") (pintype "passive"))
      (node (ref "U3") (pin "2") (pinfunction "GND_2") (pintype "passive"))
      (node (ref "U4") (pin "1") (pinfunction "1_1") (pintype "passive"))
      (node (ref "U4") (pin "C") (pinfunction "C_C") (pintype "passive"))
      (node (ref "U5") (pin "2") (pinfunction "GND_2") (pintype "passive"))
    )
    (net (code "37") (name "Net-(C1-Pad1)") (class "Default")
      (node (ref "C1") (pin "1") (pinfunction "1_1") (pintype "passive"))
      (node (ref "C2") (pin "2") (pinfunction "2_2") (pintype "passive"))
      (node (ref "R8") (pin "2") (pinfunction "2_2") (pintype "passive"))
      (node (ref "R9") (pin "2") (pinfunction "2_2") (pintype "passive"))
    )
    (net (code "38") (name "Net-(C3-Pad1)") (class "Default")
      (node (ref "C3") (pin "1") (pinfunction "1_1") (pintype "passive"))
      (node (ref "C4") (pin "2") (pinfunction "2_2") (pintype "passive"))
      (node (ref "R10") (pin "2") (pinfunction "2_2") (pintype "passive"))
      (node (ref "R11") (pin "2") (pinfunction "2_2") (pintype "passive"))
    )
    (net (code "39") (name "Net-(D37-K)") (class "Default")
      (node (ref "C1") (pin "2") (pinfunction "2_2") (pintype "passive"))
      (node (ref "D37") (pin "1") (pinfunction "K_1") (pintype "passive"))
      (node (ref "J2") (pin "2") (pinfunction "2_2") (pintype "passive"))
    )
    (net (code "40") (name "Net-(D38-K)") (class "Default")
      (node (ref "C3") (pin "2") (pinfunction "2_2") (pintype "passive"))
      (node (ref "D38") (pin "1") (pinfunction "K_1") (pintype "passive"))
      (node (ref "J3") (pin "2") (pinfunction "2_2") (pintype "passive"))
    )
    (net (code "41") (name "Net-(D40-K)") (class "Default")
      (node (ref "D40") (pin "1") (pinfunction "K_1") (pintype "passive"))
      (node (ref "J4") (pin "2") (pinfunction "2_2") (pintype "passive"))
      (node (ref "R3") (pin "1") (pinfunction "1_1") (pintype "passive"))
    )
    (net (code "42") (name "Net-(J1-CC1)") (class "Default")
      (node (ref "J1") (pin "A5") (pinfunction "CC1_A5") (pintype "passive"))
      (node (ref "R1") (pin "2") (pinfunction "2_2") (pintype "passive"))
    )
    (net (code "43") (name "Net-(J1-CC2)") (class "Default")
      (node (ref "J1") (pin "B5") (pinfunction "CC2_B5") (pintype "passive"))
      (node (ref "R2") (pin "2") (pinfunction "2_2") (pintype "passive"))
    )
    (net (code "44") (name "Net-(J5-Pad2)") (class "Default")
      (node (ref "J5") (pin "2") (pinfunction "2_2") (pintype "passive"))
      (node (ref "R7") (pin "2") (pinfunction "2_2") (pintype "passive"))
    )
    (net (code "45") (name "Net-(J5-Pad3)") (class "Default")
      (node (ref "J5") (pin "3") (pinfunction "3_3") (pintype "passive"))
      (node (ref "R6") (pin "1") (pinfunction "1_1") (pintype "passive"))
    )
    (net (code "46") (name "Net-(R15-Pad1)") (class "Default")
      (node (ref "R15") (pin "1") (pinfunction "1_1") (pintype "passive"))
      (node (ref "R4") (pin "1") (pinfunction "1_1") (pintype "passive"))
      (node (ref "U4") (pin "A") (pinfunction "A_A") (pintype "passive"))
    )
    (net (code "47") (name "Net-(R16-Pad1)") (class "Default")
      (node (ref "R16") (pin "1") (pinfunction "1_1") (pintype "passive"))
      (node (ref "R5") (pin "1") (pinfunction "1_1") (pintype "passive"))
      (node (ref "U4") (pin "B") (pinfunction "B_B") (pintype "passive"))
    )
    (net (code "48") (name "Net-(U1A-GP22)") (class "Default")
      (node (ref "R17") (pin "2") (pinfunction "2_2") (pintype "passive"))
      (node (ref "U1") (pin "29") (pinfunction "GP22_29") (pintype "bidirectional"))
    )
    (net (code "49") (name "Net-(U1B-BOOTSEL)") (class "Default")
      (node (ref "SW1") (pin "1") (pinfunction "1_1") (pintype "passive"))
      (node (ref "SW1") (pin "2") (pinfunction "2_2") (pintype "passive"))
      (node (ref "U1") (pin "TP6") (pinfunction "BOOTSEL_TP6") (pintype "passive"))
    )
    (net (code "50") (name "Net-(U3-B)") (class "Default")
      (node (ref "R7") (pin "1") (pinfunction "1_1") (pintype "passive"))
      (node (ref "U3") (pin "4") (pinfunction "B_4") (pintype "output"))
    )
    (net (code "51") (name "Net-(U3-OE)") (class "Default")
      (node (ref "R14") (pin "1") (pinfunction "1_1") (pintype "passive"))
      (node (ref "U3") (pin "5") (pinfunction "OE_5") (pintype "input"))
    )
    (net (code "52") (name "USB_VBUS") (class "Default")
      (node (ref "C11") (pin "2") (pinfunction "2_2") (pintype "passive"))
      (node (ref "J1") (pin "A4") (pinfunction "VBUS_A4") (pintype "passive"))
      (node (ref "J1") (pin "A9") (pinfunction "VBUS_A9") (pintype "passive"))
      (node (ref "J1") (pin "B4") (pinfunction "VBUS_B4") (pintype "passive"))
      (node (ref "J1") (pin "B9") (pinfunction "VBUS_B9") (pintype "passive"))
      (node (ref "R14") (pin "2") (pinfunction "2_2") (pintype "passive"))
      (node (ref "R6") (pin "2") (pinfunction "2_2") (pintype "passive"))
      (node (ref "U1") (pin "40") (pinfunction "VBUS_40") (pintype "passive"))
      (node (ref "U3") (pin "6") (pinfunction "VCCB_6") (pintype "passive"))
      (node (ref "U5") (pin "5") (pinfunction "VDD_5") (pintype "passive"))
    )
    (net (code "53") (name "unconnected-(J1-SBU1-PadA8)") (class "Default")
      (node (ref "J1") (pin "A8") (pinfunction "SBU1_A8") (pintype "passive+no_connect"))
    )
    (net (code "54") (name "unconnected-(J1-SBU2-PadB8)") (class "Default")
      (node (ref "J1") (pin "B8") (pinfunction "SBU2_B8") (pintype "passive+no_connect"))
    )
    (net (code "55") (name "unconnected-(J2-Pad3)") (class "Default")
      (node (ref "J2") (pin "3") (pinfunction "3_3") (pintype "passive+no_connect"))
    )
    (net (code "56") (name "unconnected-(J3-Pad3)") (class "Default")
      (node (ref "J3") (pin "3") (pinfunction "3_3") (pintype "passive+no_connect"))
    )
    (net (code "57") (name "unconnected-(J8-Pad3)") (class "Default")
      (node (ref "J8") (pin "3") (pinfunction "3_3") (pintype "passive"))
    )
    (net (code "58") (name "unconnected-(U1A-LED{slash}GP25-PadTP5)") (class "Default")
      (node (ref "U1") (pin "TP5") (pinfunction "LED/GP25_TP5") (pintype "bidirectional+no_connect"))
    )
    (net (code "59") (name "unconnected-(U1A-SMPS_PS{slash}GP23-PadTP4)") (class "Default")
      (node (ref "U1") (pin "TP4") (pinfunction "SMPS_PS/GP23_TP4") (pintype "bidirectional+no_connect"))
    )
    (net (code "60") (name "unconnected-(U1B-3V3_EN-Pad37)") (class "Default")
      (node (ref "U1") (pin "37") (pinfunction "3V3_EN_37") (pintype "passive+no_connect"))
    )
    (net (code "61") (name "unconnected-(U1B-RUN-Pad30)") (class "Default")
      (node (ref "U1") (pin "30") (pinfunction "RUN_30") (pintype "passive+no_connect"))
    )
    (net (code "62") (name "unconnected-(U1B-VSYS-Pad39)") (class "Default")
      (node (ref "U1") (pin "39") (pinfunction "VSYS_39") (pintype "passive"))
    )
    (net (code "63") (name "unconnected-(U4A-SHLD-Pad3)") (class "Default")
      (node (ref "U4") (pin "3") (pinfunction "SHLD_3") (pintype "passive"))
    )
    (net (code "64") (name "unconnected-(U4A-SHLD-Pad4)") (class "Default")
      (node (ref "U4") (pin "4") (pinfunction "SHLD_4") (pintype "passive"))
    )
  )
)
